# witch-pulse.net
KiCad netlist of a schematic drawn in EAGLE
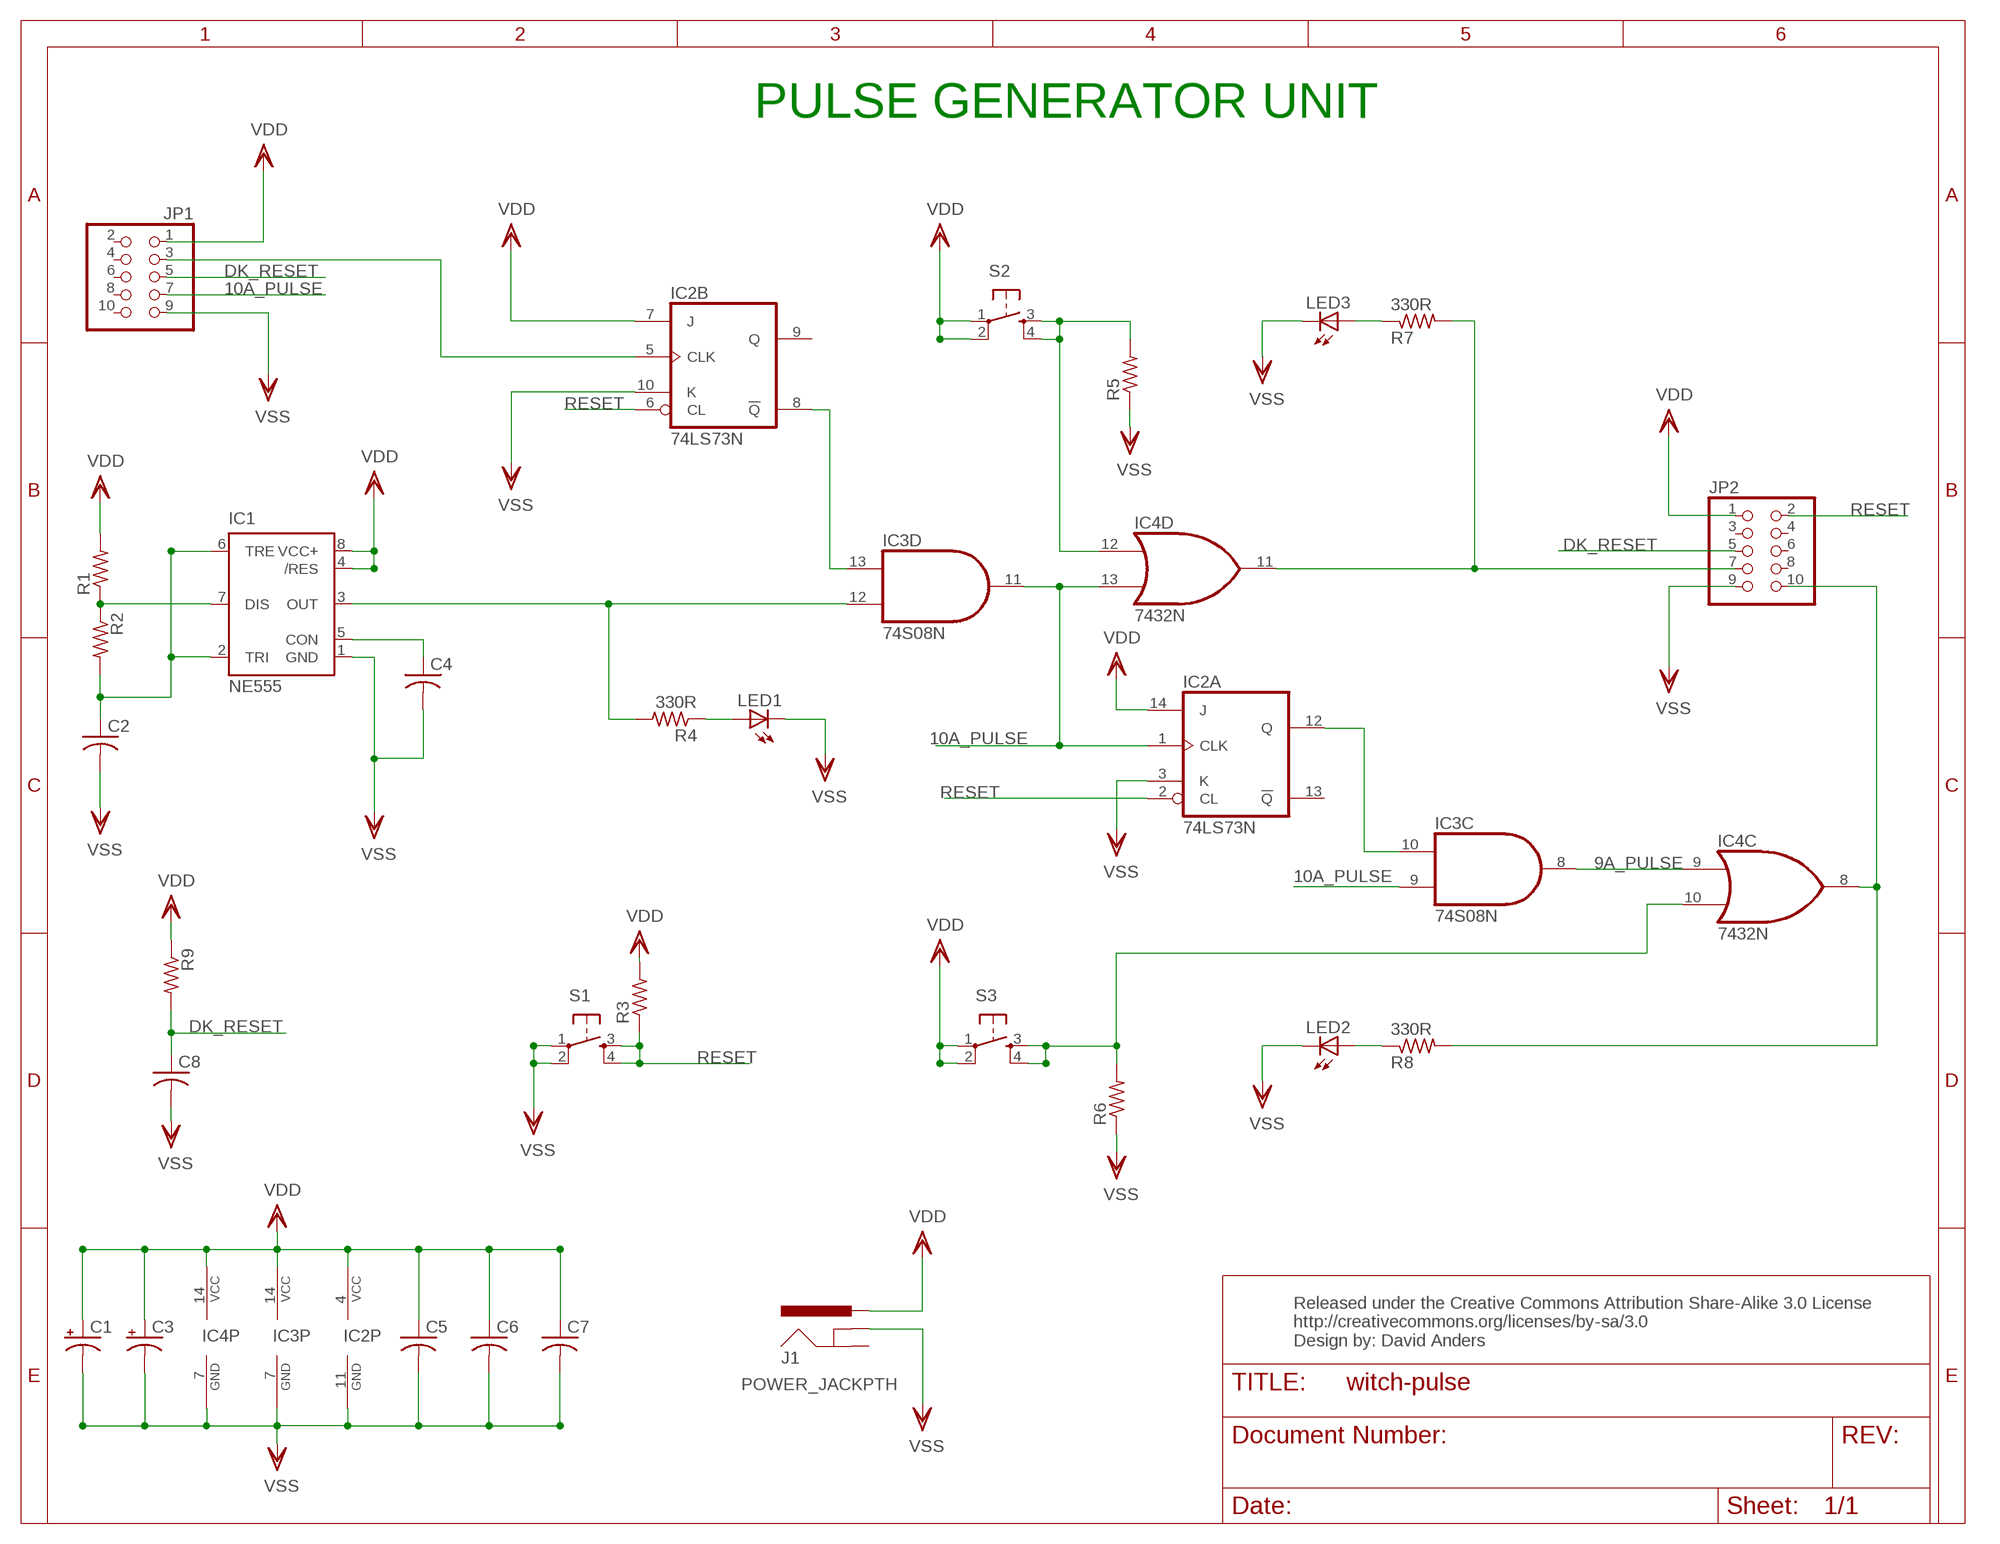
[diagram p0: schematic, sheet 1]

(export (version "E")
  (design (tool "Eeschema 10.0.6"))
  (components
    (comp (ref "C1")
      (value "CPOL-USE2.5-5")
      (footprint "eagle-import:E2,5-5")
      (libsource (lib "eagle-import") (part "CPOL-USE2.5-5"))
    )
    (comp (ref "C2")
      (value "C-US025-040X050")
      (footprint "eagle-import:C025-040X050")
      (libsource (lib "eagle-import") (part "C-US025-040X050"))
    )
    (comp (ref "C3")
      (value "CPOL-USE2.5-5")
      (footprint "eagle-import:E2,5-5")
      (libsource (lib "eagle-import") (part "CPOL-USE2.5-5"))
    )
    (comp (ref "C4")
      (value "C-US025-025X050")
      (footprint "eagle-import:C025-025X050")
      (libsource (lib "eagle-import") (part "C-US025-025X050"))
    )
    (comp (ref "C5")
      (value "C-US025-025X050")
      (footprint "eagle-import:C025-025X050")
      (libsource (lib "eagle-import") (part "C-US025-025X050"))
    )
    (comp (ref "C6")
      (value "C-US025-025X050")
      (footprint "eagle-import:C025-025X050")
      (libsource (lib "eagle-import") (part "C-US025-025X050"))
    )
    (comp (ref "C7")
      (value "C-US025-025X050")
      (footprint "eagle-import:C025-025X050")
      (libsource (lib "eagle-import") (part "C-US025-025X050"))
    )
    (comp (ref "C8")
      (value "C-US025-040X050")
      (footprint "eagle-import:C025-040X050")
      (libsource (lib "eagle-import") (part "C-US025-040X050"))
    )
    (comp (ref "IC1")
      (value "NE555")
      (footprint "eagle-import:DIL-08")
      (fields (field (name "MF") "Arrow Electronics") (field (name "MPN") "NE555N"))
      (libsource (lib "eagle-import") (part "NE555"))
    )
    (comp (ref "IC2")
      (value "74LS73N")
      (footprint "eagle-import:DIL14")
      (libsource (lib "eagle-import") (part "7473NLS"))
    )
    (comp (ref "IC3")
      (value "74S08N")
      (footprint "eagle-import:DIL14")
      (libsource (lib "eagle-import") (part "7408NS"))
    )
    (comp (ref "IC4")
      (value "7432N")
      (footprint "eagle-import:DIL14")
      (libsource (lib "eagle-import") (part "7432N"))
    )
    (comp (ref "J1")
      (value "POWER_JACKPTH")
      (footprint "eagle-import:POWER_JACK_PTH")
      (libsource (lib "eagle-import") (part "POWER_JACKPTH"))
    )
    (comp (ref "JP1")
      (value "PINHD-2X5")
      (footprint "eagle-import:2X05")
      (libsource (lib "eagle-import") (part "PINHD-2X5"))
    )
    (comp (ref "JP2")
      (value "PINHD-2X5")
      (footprint "eagle-import:2X05")
      (libsource (lib "eagle-import") (part "PINHD-2X5"))
    )
    (comp (ref "LED1")
      (value "LED5MM")
      (footprint "eagle-import:LED5MM")
      (libsource (lib "eagle-import") (part "LED5MM"))
    )
    (comp (ref "LED2")
      (value "LED5MM")
      (footprint "eagle-import:LED5MM")
      (libsource (lib "eagle-import") (part "LED5MM"))
    )
    (comp (ref "LED3")
      (value "LED5MM")
      (footprint "eagle-import:LED5MM")
      (libsource (lib "eagle-import") (part "LED5MM"))
    )
    (comp (ref "R1")
      (value "R-US_0204/5")
      (footprint "eagle-import:0204_5")
      (libsource (lib "eagle-import") (part "R-US_0204/5"))
    )
    (comp (ref "R2")
      (value "R-US_0204/5")
      (footprint "eagle-import:0204_5")
      (libsource (lib "eagle-import") (part "R-US_0204/5"))
    )
    (comp (ref "R3")
      (value "R-US_0204/5")
      (footprint "eagle-import:0204_5")
      (libsource (lib "eagle-import") (part "R-US_0204/5"))
    )
    (comp (ref "R4")
      (value "330R")
      (footprint "eagle-import:0204_5")
      (libsource (lib "eagle-import") (part "R-US_0204/5"))
    )
    (comp (ref "R5")
      (value "R-US_0204/5")
      (footprint "eagle-import:0204_5")
      (libsource (lib "eagle-import") (part "R-US_0204/5"))
    )
    (comp (ref "R6")
      (value "R-US_0204/5")
      (footprint "eagle-import:0204_5")
      (libsource (lib "eagle-import") (part "R-US_0204/5"))
    )
    (comp (ref "R7")
      (value "330R")
      (footprint "eagle-import:0204_5")
      (libsource (lib "eagle-import") (part "R-US_0204/5"))
    )
    (comp (ref "R8")
      (value "330R")
      (footprint "eagle-import:0204_5")
      (libsource (lib "eagle-import") (part "R-US_0204/5"))
    )
    (comp (ref "R9")
      (value "R-US_0204/5")
      (footprint "eagle-import:0204_5")
      (libsource (lib "eagle-import") (part "R-US_0204/5"))
    )
    (comp (ref "S1")
      (value "TAC_SWITCHPTH")
      (footprint "eagle-import:TACTILE-PTH")
      (libsource (lib "eagle-import") (part "TAC_SWITCHPTH"))
    )
    (comp (ref "S2")
      (value "TAC_SWITCHPTH")
      (footprint "eagle-import:TACTILE-PTH")
      (libsource (lib "eagle-import") (part "TAC_SWITCHPTH"))
    )
    (comp (ref "S3")
      (value "TAC_SWITCHPTH")
      (footprint "eagle-import:TACTILE-PTH")
      (libsource (lib "eagle-import") (part "TAC_SWITCHPTH"))
    )
  )
  (nets
    (net (code "1") (name "/9A_PULSE") (class "Default")
      (node (ref "IC3") (pin "8") (pinfunction "O_8") (pintype "output"))
      (node (ref "IC4") (pin "9") (pinfunction "I0_9") (pintype "input"))
    )
    (net (code "2") (name "/10A_PULSE") (class "Default")
      (node (ref "IC2") (pin "1") (pinfunction "CLK_1") (pintype "input"))
      (node (ref "IC3") (pin "11") (pinfunction "O_11") (pintype "output"))
      (node (ref "IC3") (pin "9") (pinfunction "I0_9") (pintype "input"))
      (node (ref "IC4") (pin "13") (pinfunction "I1_13") (pintype "input"))
      (node (ref "JP1") (pin "7") (pinfunction "7_7") (pintype "passive"))
    )
    (net (code "3") (name "/DK_RESET") (class "Default")
      (node (ref "C8") (pin "1") (pinfunction "1_1") (pintype "passive"))
      (node (ref "JP1") (pin "5") (pinfunction "5_5") (pintype "passive"))
      (node (ref "JP2") (pin "5") (pinfunction "5_5") (pintype "passive"))
      (node (ref "R9") (pin "2") (pinfunction "2_2") (pintype "passive"))
    )
    (net (code "4") (name "/RESET") (class "Default")
      (node (ref "IC2") (pin "2") (pinfunction "CL_2") (pintype "input"))
      (node (ref "IC2") (pin "6") (pinfunction "CL_6") (pintype "input"))
      (node (ref "JP2") (pin "2") (pinfunction "2_2") (pintype "passive"))
      (node (ref "R3") (pin "1") (pinfunction "1_1") (pintype "passive"))
      (node (ref "S1") (pin "3") (pinfunction "3_3") (pintype "passive"))
      (node (ref "S1") (pin "4") (pinfunction "4_4") (pintype "passive"))
    )
    (net (code "5") (name "Net-(IC1-CON)") (class "Default")
      (node (ref "C4") (pin "1") (pinfunction "1_1") (pintype "passive"))
      (node (ref "IC1") (pin "5") (pinfunction "CON_5") (pintype "input"))
    )
    (net (code "6") (name "Net-(IC1-DIS)") (class "Default")
      (node (ref "IC1") (pin "7") (pinfunction "DIS_7") (pintype "input"))
      (node (ref "R1") (pin "1") (pinfunction "1_1") (pintype "passive"))
      (node (ref "R2") (pin "1") (pinfunction "1_1") (pintype "passive"))
    )
    (net (code "7") (name "Net-(IC1-OUT)") (class "Default")
      (node (ref "IC1") (pin "3") (pinfunction "OUT_3") (pintype "output"))
      (node (ref "IC3") (pin "12") (pinfunction "I0_12") (pintype "input"))
      (node (ref "R4") (pin "2") (pinfunction "2_2") (pintype "passive"))
    )
    (net (code "8") (name "Net-(IC1-TRE)") (class "Default")
      (node (ref "C2") (pin "1") (pinfunction "1_1") (pintype "passive"))
      (node (ref "IC1") (pin "2") (pinfunction "TRI_2") (pintype "input"))
      (node (ref "IC1") (pin "6") (pinfunction "TRE_6") (pintype "input"))
      (node (ref "R2") (pin "2") (pinfunction "2_2") (pintype "passive"))
    )
    (net (code "9") (name "Net-(IC2A-Q)") (class "Default")
      (node (ref "IC2") (pin "12") (pinfunction "Q_12") (pintype "output"))
      (node (ref "IC3") (pin "10") (pinfunction "I1_10") (pintype "input"))
    )
    (net (code "10") (name "Net-(IC2B-CLK)") (class "Default")
      (node (ref "IC2") (pin "5") (pinfunction "CLK_5") (pintype "input"))
      (node (ref "JP1") (pin "3") (pinfunction "3_3") (pintype "passive"))
    )
    (net (code "11") (name "Net-(IC2B-~{Q})") (class "Default")
      (node (ref "IC2") (pin "8") (pinfunction "~{Q}_8") (pintype "output"))
      (node (ref "IC3") (pin "13") (pinfunction "I1_13") (pintype "input"))
    )
    (net (code "12") (name "Net-(IC4C-I1)") (class "Default")
      (node (ref "IC4") (pin "10") (pinfunction "I1_10") (pintype "input"))
      (node (ref "R6") (pin "2") (pinfunction "2_2") (pintype "passive"))
      (node (ref "S3") (pin "3") (pinfunction "3_3") (pintype "passive"))
      (node (ref "S3") (pin "4") (pinfunction "4_4") (pintype "passive"))
    )
    (net (code "13") (name "Net-(IC4C-O)") (class "Default")
      (node (ref "IC4") (pin "8") (pinfunction "O_8") (pintype "output"))
      (node (ref "JP2") (pin "10") (pinfunction "10_10") (pintype "passive"))
      (node (ref "R8") (pin "2") (pinfunction "2_2") (pintype "passive"))
    )
    (net (code "14") (name "Net-(IC4D-I0)") (class "Default")
      (node (ref "IC4") (pin "12") (pinfunction "I0_12") (pintype "input"))
      (node (ref "R5") (pin "2") (pinfunction "2_2") (pintype "passive"))
      (node (ref "S2") (pin "3") (pinfunction "3_3") (pintype "passive"))
      (node (ref "S2") (pin "4") (pinfunction "4_4") (pintype "passive"))
    )
    (net (code "15") (name "Net-(IC4D-O)") (class "Default")
      (node (ref "IC4") (pin "11") (pinfunction "O_11") (pintype "output"))
      (node (ref "JP2") (pin "7") (pinfunction "7_7") (pintype "passive"))
      (node (ref "R7") (pin "2") (pinfunction "2_2") (pintype "passive"))
    )
    (net (code "16") (name "Net-(LED1-PadA)") (class "Default")
      (node (ref "LED1") (pin "A") (pinfunction "A_A") (pintype "passive"))
      (node (ref "R4") (pin "1") (pinfunction "1_1") (pintype "passive"))
    )
    (net (code "17") (name "Net-(LED2-PadA)") (class "Default")
      (node (ref "LED2") (pin "A") (pinfunction "A_A") (pintype "passive"))
      (node (ref "R8") (pin "1") (pinfunction "1_1") (pintype "passive"))
    )
    (net (code "18") (name "Net-(LED3-PadA)") (class "Default")
      (node (ref "LED3") (pin "A") (pinfunction "A_A") (pintype "passive"))
      (node (ref "R7") (pin "1") (pinfunction "1_1") (pintype "passive"))
    )
    (net (code "19") (name "VDD") (class "Default")
      (node (ref "C1") (pin "+") (pinfunction "+_+") (pintype "passive"))
      (node (ref "C3") (pin "+") (pinfunction "+_+") (pintype "passive"))
      (node (ref "C5") (pin "1") (pinfunction "1_1") (pintype "passive"))
      (node (ref "C6") (pin "1") (pinfunction "1_1") (pintype "passive"))
      (node (ref "C7") (pin "1") (pinfunction "1_1") (pintype "passive"))
      (node (ref "IC1") (pin "4") (pinfunction "/RES_4") (pintype "input"))
      (node (ref "IC1") (pin "8") (pinfunction "VCC+_8") (pintype "power_in"))
      (node (ref "IC2") (pin "14") (pinfunction "J_14") (pintype "input"))
      (node (ref "IC2") (pin "4") (pinfunction "VCC_4") (pintype "power_in"))
      (node (ref "IC2") (pin "7") (pinfunction "J_7") (pintype "input"))
      (node (ref "IC3") (pin "14") (pinfunction "VCC_14") (pintype "power_in"))
      (node (ref "IC4") (pin "14") (pinfunction "VCC_14") (pintype "power_in"))
      (node (ref "J1") (pin "PWR") (pinfunction "PWR_PWR") (pintype "bidirectional"))
      (node (ref "JP1") (pin "1") (pinfunction "1_1") (pintype "passive"))
      (node (ref "JP2") (pin "1") (pinfunction "1_1") (pintype "passive"))
      (node (ref "R1") (pin "2") (pinfunction "2_2") (pintype "passive"))
      (node (ref "R3") (pin "2") (pinfunction "2_2") (pintype "passive"))
      (node (ref "R9") (pin "1") (pinfunction "1_1") (pintype "passive"))
      (node (ref "S2") (pin "1") (pinfunction "1_1") (pintype "passive"))
      (node (ref "S2") (pin "2") (pinfunction "2_2") (pintype "passive"))
      (node (ref "S3") (pin "1") (pinfunction "1_1") (pintype "passive"))
      (node (ref "S3") (pin "2") (pinfunction "2_2") (pintype "passive"))
    )
    (net (code "20") (name "VSS") (class "Default")
      (node (ref "C1") (pin "-") (pinfunction "-_-") (pintype "passive"))
      (node (ref "C2") (pin "2") (pinfunction "2_2") (pintype "passive"))
      (node (ref "C3") (pin "-") (pinfunction "-_-") (pintype "passive"))
      (node (ref "C4") (pin "2") (pinfunction "2_2") (pintype "passive"))
      (node (ref "C5") (pin "2") (pinfunction "2_2") (pintype "passive"))
      (node (ref "C6") (pin "2") (pinfunction "2_2") (pintype "passive"))
      (node (ref "C7") (pin "2") (pinfunction "2_2") (pintype "passive"))
      (node (ref "C8") (pin "2") (pinfunction "2_2") (pintype "passive"))
      (node (ref "IC1") (pin "1") (pinfunction "GND_1") (pintype "power_in"))
      (node (ref "IC2") (pin "10") (pinfunction "K_10") (pintype "input"))
      (node (ref "IC2") (pin "11") (pinfunction "GND_11") (pintype "power_in"))
      (node (ref "IC2") (pin "3") (pinfunction "K_3") (pintype "input"))
      (node (ref "IC3") (pin "7") (pinfunction "GND_7") (pintype "power_in"))
      (node (ref "IC4") (pin "7") (pinfunction "GND_7") (pintype "power_in"))
      (node (ref "J1") (pin "GNDBREAK") (pinfunction "GNDBREAK_GNDBREAK") (pintype "bidirectional"))
      (node (ref "JP1") (pin "9") (pinfunction "9_9") (pintype "passive"))
      (node (ref "JP2") (pin "9") (pinfunction "9_9") (pintype "passive"))
      (node (ref "LED1") (pin "K") (pinfunction "C_K") (pintype "passive"))
      (node (ref "LED2") (pin "K") (pinfunction "C_K") (pintype "passive"))
      (node (ref "LED3") (pin "K") (pinfunction "C_K") (pintype "passive"))
      (node (ref "R5") (pin "1") (pinfunction "1_1") (pintype "passive"))
      (node (ref "R6") (pin "1") (pinfunction "1_1") (pintype "passive"))
      (node (ref "S1") (pin "1") (pinfunction "1_1") (pintype "passive"))
      (node (ref "S1") (pin "2") (pinfunction "2_2") (pintype "passive"))
    )
    (net (code "21") (name "unconnected-(IC2A-~{Q}-Pad13)") (class "Default")
      (node (ref "IC2") (pin "13") (pinfunction "~{Q}_13") (pintype "output"))
    )
    (net (code "22") (name "unconnected-(IC2B-Q-Pad9)") (class "Default")
      (node (ref "IC2") (pin "9") (pinfunction "Q_9") (pintype "output"))
    )
    (net (code "23") (name "unconnected-(J1-PadGND)") (class "Default")
      (node (ref "J1") (pin "GND") (pinfunction "GND_GND") (pintype "bidirectional"))
    )
    (net (code "24") (name "unconnected-(JP1-Pad2)") (class "Default")
      (node (ref "JP1") (pin "2") (pinfunction "2_2") (pintype "passive"))
    )
    (net (code "25") (name "unconnected-(JP1-Pad4)") (class "Default")
      (node (ref "JP1") (pin "4") (pinfunction "4_4") (pintype "passive"))
    )
    (net (code "26") (name "unconnected-(JP1-Pad6)") (class "Default")
      (node (ref "JP1") (pin "6") (pinfunction "6_6") (pintype "passive"))
    )
    (net (code "27") (name "unconnected-(JP1-Pad8)") (class "Default")
      (node (ref "JP1") (pin "8") (pinfunction "8_8") (pintype "passive"))
    )
    (net (code "28") (name "unconnected-(JP1-Pad10)") (class "Default")
      (node (ref "JP1") (pin "10") (pinfunction "10_10") (pintype "passive"))
    )
    (net (code "29") (name "unconnected-(JP2-Pad3)") (class "Default")
      (node (ref "JP2") (pin "3") (pinfunction "3_3") (pintype "passive"))
    )
    (net (code "30") (name "unconnected-(JP2-Pad4)") (class "Default")
      (node (ref "JP2") (pin "4") (pinfunction "4_4") (pintype "passive"))
    )
    (net (code "31") (name "unconnected-(JP2-Pad6)") (class "Default")
      (node (ref "JP2") (pin "6") (pinfunction "6_6") (pintype "passive"))
    )
    (net (code "32") (name "unconnected-(JP2-Pad8)") (class "Default")
      (node (ref "JP2") (pin "8") (pinfunction "8_8") (pintype "passive"))
    )
  )
)
